# power.net
KiCad netlist of a schematic drawn in Altium Designer
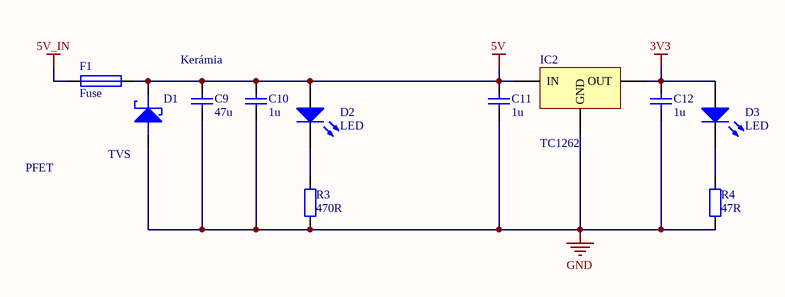
[diagram p0: power.SchDoc]

(export (version "E")
  (design (tool "Eeschema 10.0.6"))
  (components
    (comp (ref "C9")
      (value "47u")
      (footprint "FP_0805_CAP_085")
      (description "Capacitor")
      (libsource (lib "hallglib") (part "CAP"))
    )
    (comp (ref "C10")
      (value "1u")
      (footprint "FP_0805_CAP_085")
      (description "Capacitor")
      (libsource (lib "hallglib") (part "CAP"))
    )
    (comp (ref "C11")
      (value "1u")
      (footprint "FP_0805_CAP_085")
      (description "Capacitor")
      (libsource (lib "hallglib") (part "CAP"))
    )
    (comp (ref "C12")
      (value "1u")
      (footprint "FP_0805_CAP_085")
      (description "Capacitor")
      (libsource (lib "hallglib") (part "CAP"))
    )
    (comp (ref "D1")
      (value "TVS")
      (footprint "FP_SMB")
      (description "TVS diode")
      (libsource (lib "hallglib") (part "SCHOTTKY"))
    )
    (comp (ref "D2")
      (value "LED")
      (footprint "FP_0805_LED_GREEN")
      (description "Typical RED GaAs LED")
      (libsource (lib "hallglib") (part "LED"))
    )
    (comp (ref "D3")
      (value "LED")
      (footprint "FP_0805_LED_GREEN")
      (description "Typical RED GaAs LED")
      (libsource (lib "hallglib") (part "LED"))
    )
    (comp (ref "F1") (value "Fuse") (footprint "FP_MULTIFUSE") (libsource (lib "hallglib") (part "Fuse")))
    (comp (ref "IC2")
      (value "TC1262")
      (footprint "FP_SOT223")
      (description "Fixed LDO Voltage Regulator")
      (libsource (lib "mb") (part "TC1262"))
    )
    (comp (ref "R3")
      (value "470R")
      (footprint "FP_0805_RES")
      (description "Resistor")
      (libsource (lib "hallglib") (part "RES"))
    )
    (comp (ref "R4")
      (value "47R")
      (footprint "FP_0805_RES")
      (description "Resistor")
      (libsource (lib "hallglib") (part "RES"))
    )
  )
  (nets
    (net (code "1") (name "3V3") (class "Default")
      (node (ref "C12") (pin "2") (pinfunction "2_2") (pintype "passive"))
      (node (ref "D3") (pin "1") (pinfunction "A_1") (pintype "passive"))
      (node (ref "IC2") (pin "3") (pinfunction "OUT_3") (pintype "passive"))
    )
    (net (code "2") (name "5V") (class "Default")
      (node (ref "C10") (pin "2") (pinfunction "2_2") (pintype "passive"))
      (node (ref "C11") (pin "2") (pinfunction "2_2") (pintype "passive"))
      (node (ref "C9") (pin "2") (pinfunction "2_2") (pintype "passive"))
      (node (ref "D1") (pin "1") (pinfunction "CATHODE_1") (pintype "passive"))
      (node (ref "D2") (pin "1") (pinfunction "A_1") (pintype "passive"))
      (node (ref "F1") (pin "2") (pinfunction "2_2") (pintype "passive"))
      (node (ref "IC2") (pin "1") (pinfunction "IN_1") (pintype "passive"))
    )
    (net (code "3") (name "5V_IN") (class "Default")
      (node (ref "F1") (pin "1") (pinfunction "1_1") (pintype "passive"))
    )
    (net (code "4") (name "GND") (class "Default")
      (node (ref "C10") (pin "1") (pinfunction "1_1") (pintype "passive"))
      (node (ref "C11") (pin "1") (pinfunction "1_1") (pintype "passive"))
      (node (ref "C12") (pin "1") (pinfunction "1_1") (pintype "passive"))
      (node (ref "C9") (pin "1") (pinfunction "1_1") (pintype "passive"))
      (node (ref "D1") (pin "2") (pinfunction "ANODE_2") (pintype "passive"))
      (node (ref "IC2") (pin "2") (pinfunction "GND_2") (pintype "passive"))
      (node (ref "R3") (pin "1") (pinfunction "1_1") (pintype "passive"))
      (node (ref "R4") (pin "1") (pinfunction "1_1") (pintype "passive"))
    )
    (net (code "5") (name "Net-(D2-K)") (class "Default")
      (node (ref "D2") (pin "2") (pinfunction "K_2") (pintype "passive"))
      (node (ref "R3") (pin "2") (pinfunction "2_2") (pintype "passive"))
    )
    (net (code "6") (name "Net-(D3-K)") (class "Default")
      (node (ref "D3") (pin "2") (pinfunction "K_2") (pintype "passive"))
      (node (ref "R4") (pin "2") (pinfunction "2_2") (pintype "passive"))
    )
  )
)
